# 17_FPGA_decoupling.net
KiCad netlist of a schematic drawn in Altium Designer
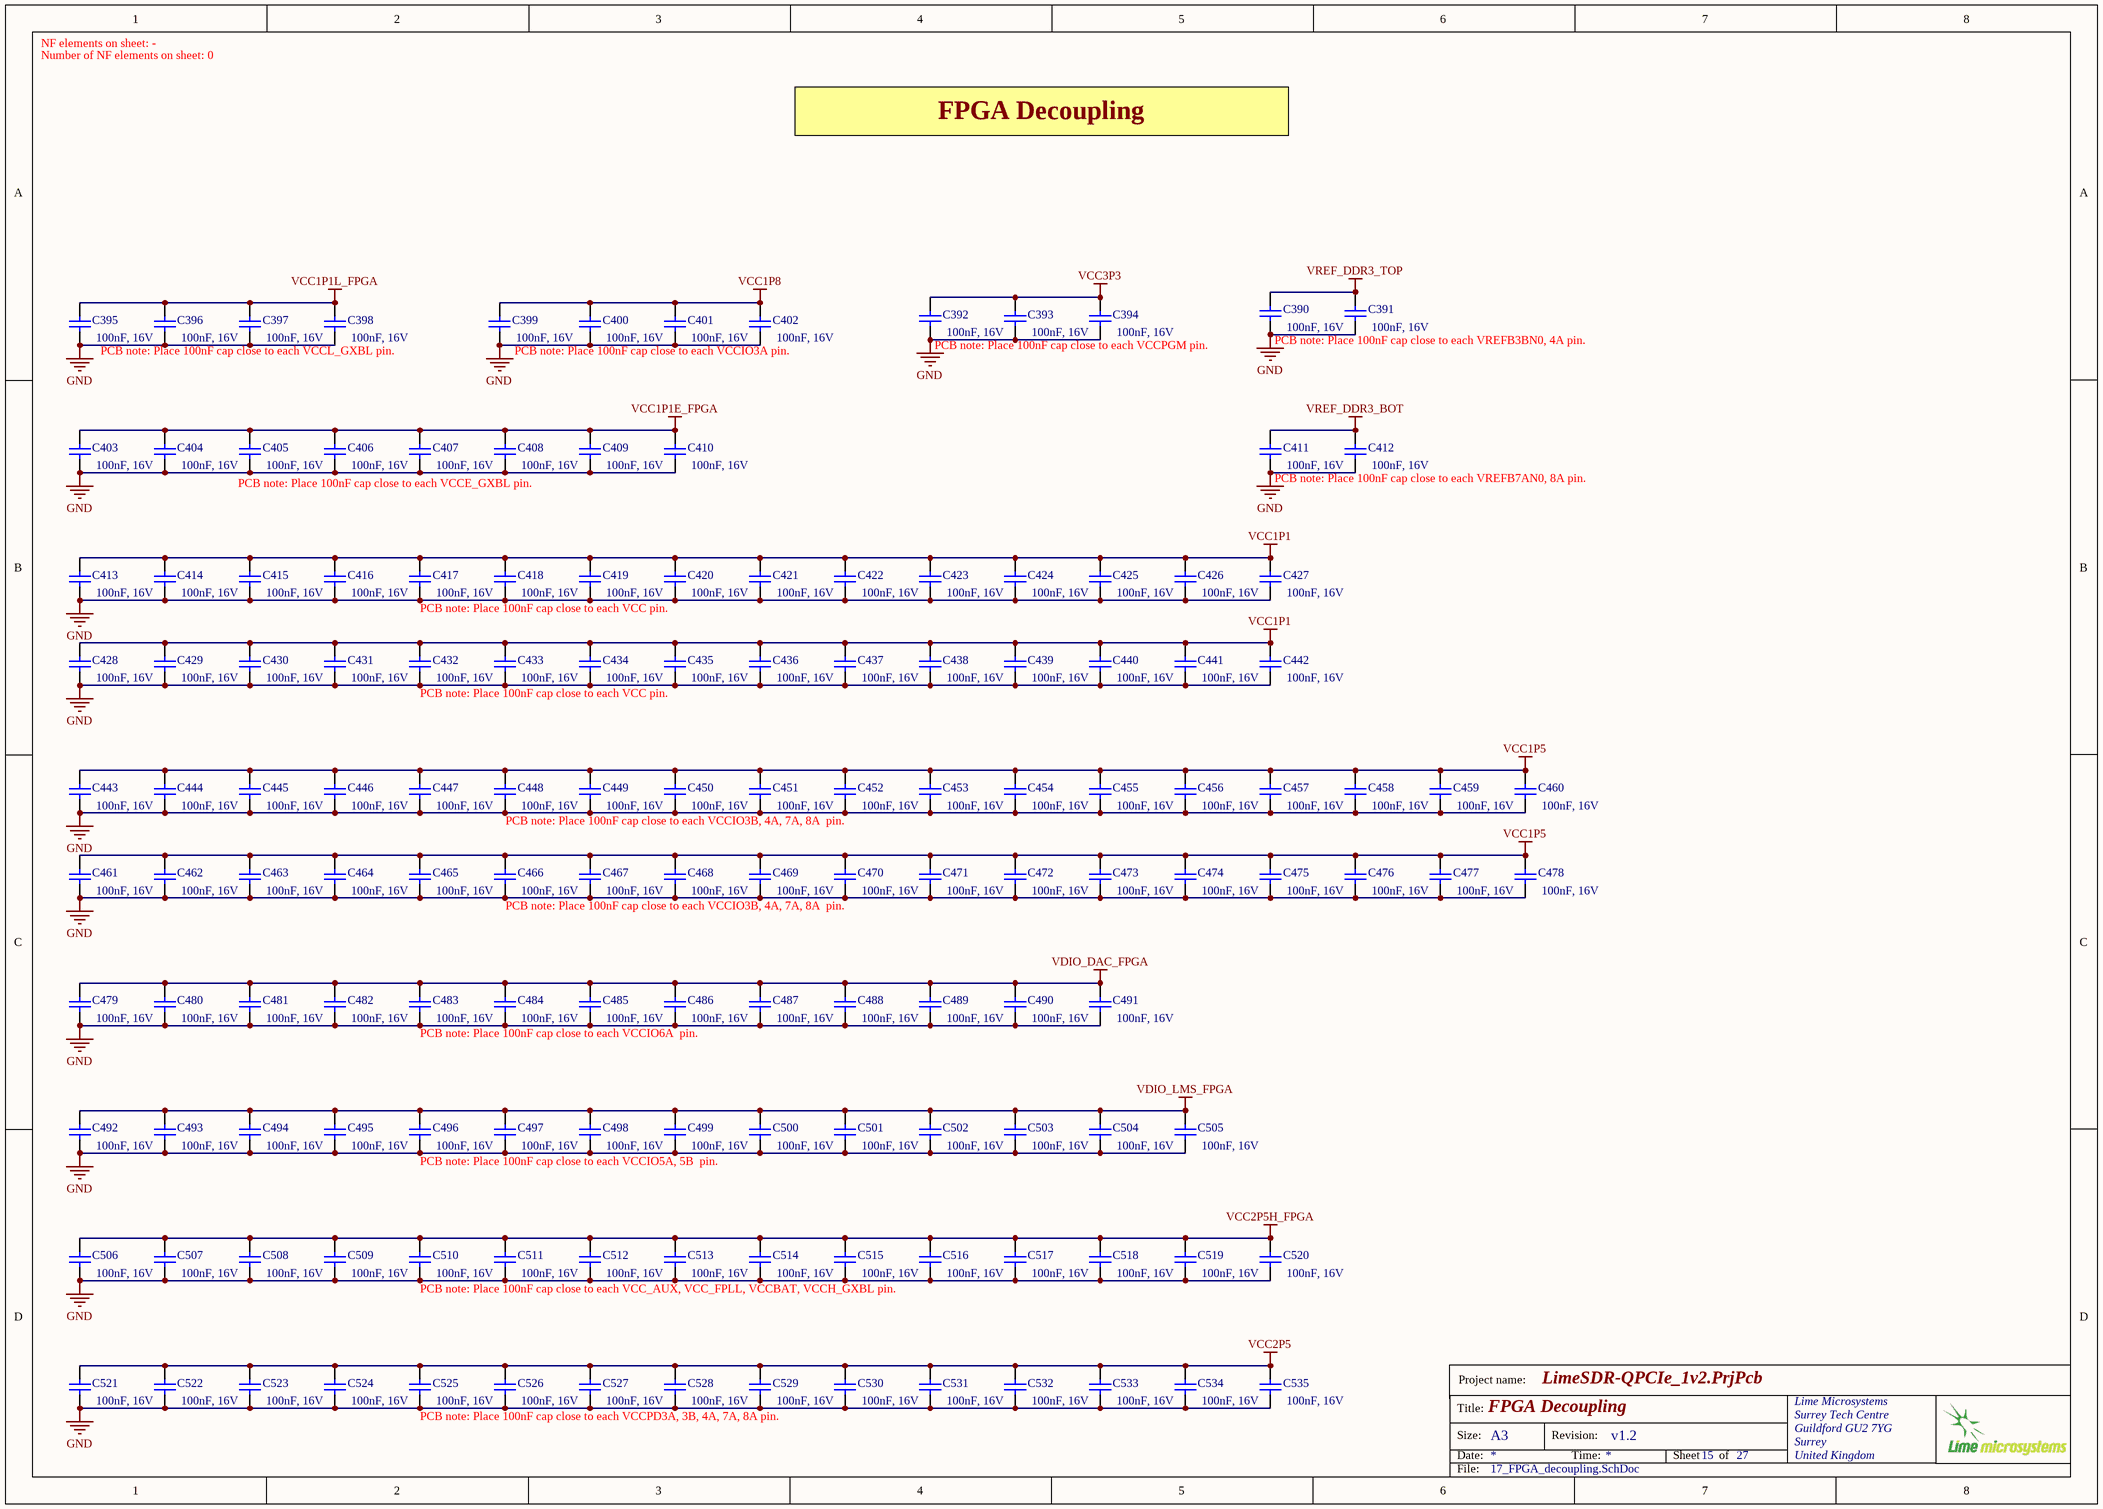
[diagram p0: 17_FPGA_decoupling.SchDoc]

(export (version "E")
  (design (tool "Eeschema 10.0.6"))
  (components
    (comp (ref "C390")
      (value "100nF, 16V")
      (footprint "CAP0402")
      (fields
        (field (name "TOLERANCE") "10 %")
        (field (name "MANUFACTURER") "Murata Electronics")
        (field (name "MANUFACTURER PART NUMBER") "GRM155R71C104KA88D")
      )
      (libsource (lib "LimeFPGAboard_schLib") (part "Cap_0603"))
    )
    (comp (ref "C391")
      (value "100nF, 16V")
      (footprint "CAP0402")
      (fields
        (field (name "TOLERANCE") "10 %")
        (field (name "MANUFACTURER") "Murata Electronics")
        (field (name "MANUFACTURER PART NUMBER") "GRM155R71C104KA88D")
      )
      (libsource (lib "LimeFPGAboard_schLib") (part "Cap_0603"))
    )
    (comp (ref "C392")
      (value "100nF, 16V")
      (footprint "CAP0402")
      (fields
        (field (name "TOLERANCE") "10 %")
        (field (name "MANUFACTURER") "Murata Electronics")
        (field (name "MANUFACTURER PART NUMBER") "GRM155R71C104KA88D")
      )
      (libsource (lib "LimeFPGAboard_schLib") (part "Cap_0603"))
    )
    (comp (ref "C393")
      (value "100nF, 16V")
      (footprint "CAP0402")
      (fields
        (field (name "TOLERANCE") "10 %")
        (field (name "MANUFACTURER") "Murata Electronics")
        (field (name "MANUFACTURER PART NUMBER") "GRM155R71C104KA88D")
      )
      (libsource (lib "LimeFPGAboard_schLib") (part "Cap_0603"))
    )
    (comp (ref "C394")
      (value "100nF, 16V")
      (footprint "CAP0402")
      (fields
        (field (name "TOLERANCE") "10 %")
        (field (name "MANUFACTURER") "Murata Electronics")
        (field (name "MANUFACTURER PART NUMBER") "GRM155R71C104KA88D")
      )
      (libsource (lib "LimeFPGAboard_schLib") (part "Cap_0603"))
    )
    (comp (ref "C395")
      (value "100nF, 16V")
      (footprint "CAP0402")
      (fields
        (field (name "TOLERANCE") "10 %")
        (field (name "MANUFACTURER") "Murata Electronics")
        (field (name "MANUFACTURER PART NUMBER") "GRM155R71C104KA88D")
      )
      (libsource (lib "LimeFPGAboard_schLib") (part "Cap_0603"))
    )
    (comp (ref "C396")
      (value "100nF, 16V")
      (footprint "CAP0402")
      (fields
        (field (name "TOLERANCE") "10 %")
        (field (name "MANUFACTURER") "Murata Electronics")
        (field (name "MANUFACTURER PART NUMBER") "GRM155R71C104KA88D")
      )
      (libsource (lib "LimeFPGAboard_schLib") (part "Cap_0603"))
    )
    (comp (ref "C397")
      (value "100nF, 16V")
      (footprint "CAP0402")
      (fields
        (field (name "TOLERANCE") "10 %")
        (field (name "MANUFACTURER") "Murata Electronics")
        (field (name "MANUFACTURER PART NUMBER") "GRM155R71C104KA88D")
      )
      (libsource (lib "LimeFPGAboard_schLib") (part "Cap_0603"))
    )
    (comp (ref "C398")
      (value "100nF, 16V")
      (footprint "CAP0402")
      (fields
        (field (name "TOLERANCE") "10 %")
        (field (name "MANUFACTURER") "Murata Electronics")
        (field (name "MANUFACTURER PART NUMBER") "GRM155R71C104KA88D")
      )
      (libsource (lib "LimeFPGAboard_schLib") (part "Cap_0603"))
    )
    (comp (ref "C399")
      (value "100nF, 16V")
      (footprint "CAP0402")
      (fields
        (field (name "TOLERANCE") "10 %")
        (field (name "MANUFACTURER") "Murata Electronics")
        (field (name "MANUFACTURER PART NUMBER") "GRM155R71C104KA88D")
      )
      (libsource (lib "LimeFPGAboard_schLib") (part "Cap_0603"))
    )
    (comp (ref "C400")
      (value "100nF, 16V")
      (footprint "CAP0402")
      (fields
        (field (name "TOLERANCE") "10 %")
        (field (name "MANUFACTURER") "Murata Electronics")
        (field (name "MANUFACTURER PART NUMBER") "GRM155R71C104KA88D")
      )
      (libsource (lib "LimeFPGAboard_schLib") (part "Cap_0603"))
    )
    (comp (ref "C401")
      (value "100nF, 16V")
      (footprint "CAP0402")
      (fields
        (field (name "TOLERANCE") "10 %")
        (field (name "MANUFACTURER") "Murata Electronics")
        (field (name "MANUFACTURER PART NUMBER") "GRM155R71C104KA88D")
      )
      (libsource (lib "LimeFPGAboard_schLib") (part "Cap_0603"))
    )
    (comp (ref "C402")
      (value "100nF, 16V")
      (footprint "CAP0402")
      (fields
        (field (name "TOLERANCE") "10 %")
        (field (name "MANUFACTURER") "Murata Electronics")
        (field (name "MANUFACTURER PART NUMBER") "GRM155R71C104KA88D")
      )
      (libsource (lib "LimeFPGAboard_schLib") (part "Cap_0603"))
    )
    (comp (ref "C403")
      (value "100nF, 16V")
      (footprint "CAP0402")
      (fields
        (field (name "TOLERANCE") "10 %")
        (field (name "MANUFACTURER") "Murata Electronics")
        (field (name "MANUFACTURER PART NUMBER") "GRM155R71C104KA88D")
      )
      (libsource (lib "LimeFPGAboard_schLib") (part "Cap_0603"))
    )
    (comp (ref "C404")
      (value "100nF, 16V")
      (footprint "CAP0402")
      (fields
        (field (name "TOLERANCE") "10 %")
        (field (name "MANUFACTURER") "Murata Electronics")
        (field (name "MANUFACTURER PART NUMBER") "GRM155R71C104KA88D")
      )
      (libsource (lib "LimeFPGAboard_schLib") (part "Cap_0603"))
    )
    (comp (ref "C405")
      (value "100nF, 16V")
      (footprint "CAP0402")
      (fields
        (field (name "TOLERANCE") "10 %")
        (field (name "MANUFACTURER") "Murata Electronics")
        (field (name "MANUFACTURER PART NUMBER") "GRM155R71C104KA88D")
      )
      (libsource (lib "LimeFPGAboard_schLib") (part "Cap_0603"))
    )
    (comp (ref "C406")
      (value "100nF, 16V")
      (footprint "CAP0402")
      (fields
        (field (name "TOLERANCE") "10 %")
        (field (name "MANUFACTURER") "Murata Electronics")
        (field (name "MANUFACTURER PART NUMBER") "GRM155R71C104KA88D")
      )
      (libsource (lib "LimeFPGAboard_schLib") (part "Cap_0603"))
    )
    (comp (ref "C407")
      (value "100nF, 16V")
      (footprint "CAP0402")
      (fields
        (field (name "TOLERANCE") "10 %")
        (field (name "MANUFACTURER") "Murata Electronics")
        (field (name "MANUFACTURER PART NUMBER") "GRM155R71C104KA88D")
      )
      (libsource (lib "LimeFPGAboard_schLib") (part "Cap_0603"))
    )
    (comp (ref "C408")
      (value "100nF, 16V")
      (footprint "CAP0402")
      (fields
        (field (name "TOLERANCE") "10 %")
        (field (name "MANUFACTURER") "Murata Electronics")
        (field (name "MANUFACTURER PART NUMBER") "GRM155R71C104KA88D")
      )
      (libsource (lib "LimeFPGAboard_schLib") (part "Cap_0603"))
    )
    (comp (ref "C409")
      (value "100nF, 16V")
      (footprint "CAP0402")
      (fields
        (field (name "TOLERANCE") "10 %")
        (field (name "MANUFACTURER") "Murata Electronics")
        (field (name "MANUFACTURER PART NUMBER") "GRM155R71C104KA88D")
      )
      (libsource (lib "LimeFPGAboard_schLib") (part "Cap_0603"))
    )
    (comp (ref "C410")
      (value "100nF, 16V")
      (footprint "CAP0402")
      (fields
        (field (name "TOLERANCE") "10 %")
        (field (name "MANUFACTURER") "Murata Electronics")
        (field (name "MANUFACTURER PART NUMBER") "GRM155R71C104KA88D")
      )
      (libsource (lib "LimeFPGAboard_schLib") (part "Cap_0603"))
    )
    (comp (ref "C411")
      (value "100nF, 16V")
      (footprint "CAP0402")
      (fields
        (field (name "TOLERANCE") "10 %")
        (field (name "MANUFACTURER") "Murata Electronics")
        (field (name "MANUFACTURER PART NUMBER") "GRM155R71C104KA88D")
      )
      (libsource (lib "LimeFPGAboard_schLib") (part "Cap_0603"))
    )
    (comp (ref "C412")
      (value "100nF, 16V")
      (footprint "CAP0402")
      (fields
        (field (name "TOLERANCE") "10 %")
        (field (name "MANUFACTURER") "Murata Electronics")
        (field (name "MANUFACTURER PART NUMBER") "GRM155R71C104KA88D")
      )
      (libsource (lib "LimeFPGAboard_schLib") (part "Cap_0603"))
    )
    (comp (ref "C413")
      (value "100nF, 16V")
      (footprint "CAP0402")
      (fields
        (field (name "TOLERANCE") "10 %")
        (field (name "MANUFACTURER") "Murata Electronics")
        (field (name "MANUFACTURER PART NUMBER") "GRM155R71C104KA88D")
      )
      (libsource (lib "LimeFPGAboard_schLib") (part "Cap_0603"))
    )
    (comp (ref "C414")
      (value "100nF, 16V")
      (footprint "CAP0402")
      (fields
        (field (name "TOLERANCE") "10 %")
        (field (name "MANUFACTURER") "Murata Electronics")
        (field (name "MANUFACTURER PART NUMBER") "GRM155R71C104KA88D")
      )
      (libsource (lib "LimeFPGAboard_schLib") (part "Cap_0603"))
    )
    (comp (ref "C415")
      (value "100nF, 16V")
      (footprint "CAP0402")
      (fields
        (field (name "TOLERANCE") "10 %")
        (field (name "MANUFACTURER") "Murata Electronics")
        (field (name "MANUFACTURER PART NUMBER") "GRM155R71C104KA88D")
      )
      (libsource (lib "LimeFPGAboard_schLib") (part "Cap_0603"))
    )
    (comp (ref "C416")
      (value "100nF, 16V")
      (footprint "CAP0402")
      (fields
        (field (name "TOLERANCE") "10 %")
        (field (name "MANUFACTURER") "Murata Electronics")
        (field (name "MANUFACTURER PART NUMBER") "GRM155R71C104KA88D")
      )
      (libsource (lib "LimeFPGAboard_schLib") (part "Cap_0603"))
    )
    (comp (ref "C417")
      (value "100nF, 16V")
      (footprint "CAP0402")
      (fields
        (field (name "TOLERANCE") "10 %")
        (field (name "MANUFACTURER") "Murata Electronics")
        (field (name "MANUFACTURER PART NUMBER") "GRM155R71C104KA88D")
      )
      (libsource (lib "LimeFPGAboard_schLib") (part "Cap_0603"))
    )
    (comp (ref "C418")
      (value "100nF, 16V")
      (footprint "CAP0402")
      (fields
        (field (name "TOLERANCE") "10 %")
        (field (name "MANUFACTURER") "Murata Electronics")
        (field (name "MANUFACTURER PART NUMBER") "GRM155R71C104KA88D")
      )
      (libsource (lib "LimeFPGAboard_schLib") (part "Cap_0603"))
    )
    (comp (ref "C419")
      (value "100nF, 16V")
      (footprint "CAP0402")
      (fields
        (field (name "TOLERANCE") "10 %")
        (field (name "MANUFACTURER") "Murata Electronics")
        (field (name "MANUFACTURER PART NUMBER") "GRM155R71C104KA88D")
      )
      (libsource (lib "LimeFPGAboard_schLib") (part "Cap_0603"))
    )
    (comp (ref "C420")
      (value "100nF, 16V")
      (footprint "CAP0402")
      (fields
        (field (name "TOLERANCE") "10 %")
        (field (name "MANUFACTURER") "Murata Electronics")
        (field (name "MANUFACTURER PART NUMBER") "GRM155R71C104KA88D")
      )
      (libsource (lib "LimeFPGAboard_schLib") (part "Cap_0603"))
    )
    (comp (ref "C421")
      (value "100nF, 16V")
      (footprint "CAP0402")
      (fields
        (field (name "TOLERANCE") "10 %")
        (field (name "MANUFACTURER") "Murata Electronics")
        (field (name "MANUFACTURER PART NUMBER") "GRM155R71C104KA88D")
      )
      (libsource (lib "LimeFPGAboard_schLib") (part "Cap_0603"))
    )
    (comp (ref "C422")
      (value "100nF, 16V")
      (footprint "CAP0402")
      (fields
        (field (name "TOLERANCE") "10 %")
        (field (name "MANUFACTURER") "Murata Electronics")
        (field (name "MANUFACTURER PART NUMBER") "GRM155R71C104KA88D")
      )
      (libsource (lib "LimeFPGAboard_schLib") (part "Cap_0603"))
    )
    (comp (ref "C423")
      (value "100nF, 16V")
      (footprint "CAP0402")
      (fields
        (field (name "TOLERANCE") "10 %")
        (field (name "MANUFACTURER") "Murata Electronics")
        (field (name "MANUFACTURER PART NUMBER") "GRM155R71C104KA88D")
      )
      (libsource (lib "LimeFPGAboard_schLib") (part "Cap_0603"))
    )
    (comp (ref "C424")
      (value "100nF, 16V")
      (footprint "CAP0402")
      (fields
        (field (name "TOLERANCE") "10 %")
        (field (name "MANUFACTURER") "Murata Electronics")
        (field (name "MANUFACTURER PART NUMBER") "GRM155R71C104KA88D")
      )
      (libsource (lib "LimeFPGAboard_schLib") (part "Cap_0603"))
    )
    (comp (ref "C425")
      (value "100nF, 16V")
      (footprint "CAP0402")
      (fields
        (field (name "TOLERANCE") "10 %")
        (field (name "MANUFACTURER") "Murata Electronics")
        (field (name "MANUFACTURER PART NUMBER") "GRM155R71C104KA88D")
      )
      (libsource (lib "LimeFPGAboard_schLib") (part "Cap_0603"))
    )
    (comp (ref "C426")
      (value "100nF, 16V")
      (footprint "CAP0402")
      (fields
        (field (name "TOLERANCE") "10 %")
        (field (name "MANUFACTURER") "Murata Electronics")
        (field (name "MANUFACTURER PART NUMBER") "GRM155R71C104KA88D")
      )
      (libsource (lib "LimeFPGAboard_schLib") (part "Cap_0603"))
    )
    (comp (ref "C427")
      (value "100nF, 16V")
      (footprint "CAP0402")
      (fields
        (field (name "TOLERANCE") "10 %")
        (field (name "MANUFACTURER") "Murata Electronics")
        (field (name "MANUFACTURER PART NUMBER") "GRM155R71C104KA88D")
      )
      (libsource (lib "LimeFPGAboard_schLib") (part "Cap_0603"))
    )
    (comp (ref "C428")
      (value "100nF, 16V")
      (footprint "CAP0402")
      (fields
        (field (name "TOLERANCE") "10 %")
        (field (name "MANUFACTURER") "Murata Electronics")
        (field (name "MANUFACTURER PART NUMBER") "GRM155R71C104KA88D")
      )
      (libsource (lib "LimeFPGAboard_schLib") (part "Cap_0603"))
    )
    (comp (ref "C429")
      (value "100nF, 16V")
      (footprint "CAP0402")
      (fields
        (field (name "TOLERANCE") "10 %")
        (field (name "MANUFACTURER") "Murata Electronics")
        (field (name "MANUFACTURER PART NUMBER") "GRM155R71C104KA88D")
      )
      (libsource (lib "LimeFPGAboard_schLib") (part "Cap_0603"))
    )
    (comp (ref "C430")
      (value "100nF, 16V")
      (footprint "CAP0402")
      (fields
        (field (name "TOLERANCE") "10 %")
        (field (name "MANUFACTURER") "Murata Electronics")
        (field (name "MANUFACTURER PART NUMBER") "GRM155R71C104KA88D")
      )
      (libsource (lib "LimeFPGAboard_schLib") (part "Cap_0603"))
    )
    (comp (ref "C431")
      (value "100nF, 16V")
      (footprint "CAP0402")
      (fields
        (field (name "TOLERANCE") "10 %")
        (field (name "MANUFACTURER") "Murata Electronics")
        (field (name "MANUFACTURER PART NUMBER") "GRM155R71C104KA88D")
      )
      (libsource (lib "LimeFPGAboard_schLib") (part "Cap_0603"))
    )
    (comp (ref "C432")
      (value "100nF, 16V")
      (footprint "CAP0402")
      (fields
        (field (name "TOLERANCE") "10 %")
        (field (name "MANUFACTURER") "Murata Electronics")
        (field (name "MANUFACTURER PART NUMBER") "GRM155R71C104KA88D")
      )
      (libsource (lib "LimeFPGAboard_schLib") (part "Cap_0603"))
    )
    (comp (ref "C433")
      (value "100nF, 16V")
      (footprint "CAP0402")
      (fields
        (field (name "TOLERANCE") "10 %")
        (field (name "MANUFACTURER") "Murata Electronics")
        (field (name "MANUFACTURER PART NUMBER") "GRM155R71C104KA88D")
      )
      (libsource (lib "LimeFPGAboard_schLib") (part "Cap_0603"))
    )
    (comp (ref "C434")
      (value "100nF, 16V")
      (footprint "CAP0402")
      (fields
        (field (name "TOLERANCE") "10 %")
        (field (name "MANUFACTURER") "Murata Electronics")
        (field (name "MANUFACTURER PART NUMBER") "GRM155R71C104KA88D")
      )
      (libsource (lib "LimeFPGAboard_schLib") (part "Cap_0603"))
    )
    (comp (ref "C435")
      (value "100nF, 16V")
      (footprint "CAP0402")
      (fields
        (field (name "TOLERANCE") "10 %")
        (field (name "MANUFACTURER") "Murata Electronics")
        (field (name "MANUFACTURER PART NUMBER") "GRM155R71C104KA88D")
      )
      (libsource (lib "LimeFPGAboard_schLib") (part "Cap_0603"))
    )
    (comp (ref "C436")
      (value "100nF, 16V")
      (footprint "CAP0402")
      (fields
        (field (name "TOLERANCE") "10 %")
        (field (name "MANUFACTURER") "Murata Electronics")
        (field (name "MANUFACTURER PART NUMBER") "GRM155R71C104KA88D")
      )
      (libsource (lib "LimeFPGAboard_schLib") (part "Cap_0603"))
    )
    (comp (ref "C437")
      (value "100nF, 16V")
      (footprint "CAP0402")
      (fields
        (field (name "TOLERANCE") "10 %")
        (field (name "MANUFACTURER") "Murata Electronics")
        (field (name "MANUFACTURER PART NUMBER") "GRM155R71C104KA88D")
      )
      (libsource (lib "LimeFPGAboard_schLib") (part "Cap_0603"))
    )
    (comp (ref "C438")
      (value "100nF, 16V")
      (footprint "CAP0402")
      (fields
        (field (name "TOLERANCE") "10 %")
        (field (name "MANUFACTURER") "Murata Electronics")
        (field (name "MANUFACTURER PART NUMBER") "GRM155R71C104KA88D")
      )
      (libsource (lib "LimeFPGAboard_schLib") (part "Cap_0603"))
    )
    (comp (ref "C439")
      (value "100nF, 16V")
      (footprint "CAP0402")
      (fields
        (field (name "TOLERANCE") "10 %")
        (field (name "MANUFACTURER") "Murata Electronics")
        (field (name "MANUFACTURER PART NUMBER") "GRM155R71C104KA88D")
      )
      (libsource (lib "LimeFPGAboard_schLib") (part "Cap_0603"))
    )
    (comp (ref "C440")
      (value "100nF, 16V")
      (footprint "CAP0402")
      (fields
        (field (name "TOLERANCE") "10 %")
        (field (name "MANUFACTURER") "Murata Electronics")
        (field (name "MANUFACTURER PART NUMBER") "GRM155R71C104KA88D")
      )
      (libsource (lib "LimeFPGAboard_schLib") (part "Cap_0603"))
    )
    (comp (ref "C441")
      (value "100nF, 16V")
      (footprint "CAP0402")
      (fields
        (field (name "TOLERANCE") "10 %")
        (field (name "MANUFACTURER") "Murata Electronics")
        (field (name "MANUFACTURER PART NUMBER") "GRM155R71C104KA88D")
      )
      (libsource (lib "LimeFPGAboard_schLib") (part "Cap_0603"))
    )
    (comp (ref "C442")
      (value "100nF, 16V")
      (footprint "CAP0402")
      (fields
        (field (name "TOLERANCE") "10 %")
        (field (name "MANUFACTURER") "Murata Electronics")
        (field (name "MANUFACTURER PART NUMBER") "GRM155R71C104KA88D")
      )
      (libsource (lib "LimeFPGAboard_schLib") (part "Cap_0603"))
    )
    (comp (ref "C443")
      (value "100nF, 16V")
      (footprint "CAP0402")
      (fields
        (field (name "TOLERANCE") "10 %")
        (field (name "MANUFACTURER") "Murata Electronics")
        (field (name "MANUFACTURER PART NUMBER") "GRM155R71C104KA88D")
      )
      (libsource (lib "LimeFPGAboard_schLib") (part "Cap_0603"))
    )
    (comp (ref "C444")
      (value "100nF, 16V")
      (footprint "CAP0402")
      (fields
        (field (name "TOLERANCE") "10 %")
        (field (name "MANUFACTURER") "Murata Electronics")
        (field (name "MANUFACTURER PART NUMBER") "GRM155R71C104KA88D")
      )
      (libsource (lib "LimeFPGAboard_schLib") (part "Cap_0603"))
    )
    (comp (ref "C445")
      (value "100nF, 16V")
      (footprint "CAP0402")
      (fields
        (field (name "TOLERANCE") "10 %")
        (field (name "MANUFACTURER") "Murata Electronics")
        (field (name "MANUFACTURER PART NUMBER") "GRM155R71C104KA88D")
      )
      (libsource (lib "LimeFPGAboard_schLib") (part "Cap_0603"))
    )
    (comp (ref "C446")
      (value "100nF, 16V")
      (footprint "CAP0402")
      (fields
        (field (name "TOLERANCE") "10 %")
        (field (name "MANUFACTURER") "Murata Electronics")
        (field (name "MANUFACTURER PART NUMBER") "GRM155R71C104KA88D")
      )
      (libsource (lib "LimeFPGAboard_schLib") (part "Cap_0603"))
    )
    (comp (ref "C447")
      (value "100nF, 16V")
      (footprint "CAP0402")
      (fields
        (field (name "TOLERANCE") "10 %")
        (field (name "MANUFACTURER") "Murata Electronics")
        (field (name "MANUFACTURER PART NUMBER") "GRM155R71C104KA88D")
      )
      (libsource (lib "LimeFPGAboard_schLib") (part "Cap_0603"))
    )
    (comp (ref "C448")
      (value "100nF, 16V")
      (footprint "CAP0402")
      (fields
        (field (name "TOLERANCE") "10 %")
        (field (name "MANUFACTURER") "Murata Electronics")
        (field (name "MANUFACTURER PART NUMBER") "GRM155R71C104KA88D")
      )
      (libsource (lib "LimeFPGAboard_schLib") (part "Cap_0603"))
    )
    (comp (ref "C449")
      (value "100nF, 16V")
      (footprint "CAP0402")
      (fields
        (field (name "TOLERANCE") "10 %")
        (field (name "MANUFACTURER") "Murata Electronics")
        (field (name "MANUFACTURER PART NUMBER") "GRM155R71C104KA88D")
      )
      (libsource (lib "LimeFPGAboard_schLib") (part "Cap_0603"))
    )
    (comp (ref "C450")
      (value "100nF, 16V")
      (footprint "CAP0402")
      (fields
        (field (name "TOLERANCE") "10 %")
        (field (name "MANUFACTURER") "Murata Electronics")
        (field (name "MANUFACTURER PART NUMBER") "GRM155R71C104KA88D")
      )
      (libsource (lib "LimeFPGAboard_schLib") (part "Cap_0603"))
    )
    (comp (ref "C451")
      (value "100nF, 16V")
      (footprint "CAP0402")
      (fields
        (field (name "TOLERANCE") "10 %")
        (field (name "MANUFACTURER") "Murata Electronics")
        (field (name "MANUFACTURER PART NUMBER") "GRM155R71C104KA88D")
      )
      (libsource (lib "LimeFPGAboard_schLib") (part "Cap_0603"))
    )
    (comp (ref "C452")
      (value "100nF, 16V")
      (footprint "CAP0402")
      (fields
        (field (name "TOLERANCE") "10 %")
        (field (name "MANUFACTURER") "Murata Electronics")
        (field (name "MANUFACTURER PART NUMBER") "GRM155R71C104KA88D")
      )
      (libsource (lib "LimeFPGAboard_schLib") (part "Cap_0603"))
    )
    (comp (ref "C453")
      (value "100nF, 16V")
      (footprint "CAP0402")
      (fields
        (field (name "TOLERANCE") "10 %")
        (field (name "MANUFACTURER") "Murata Electronics")
        (field (name "MANUFACTURER PART NUMBER") "GRM155R71C104KA88D")
      )
      (libsource (lib "LimeFPGAboard_schLib") (part "Cap_0603"))
    )
    (comp (ref "C454")
      (value "100nF, 16V")
      (footprint "CAP0402")
      (fields
        (field (name "TOLERANCE") "10 %")
        (field (name "MANUFACTURER") "Murata Electronics")
        (field (name "MANUFACTURER PART NUMBER") "GRM155R71C104KA88D")
      )
      (libsource (lib "LimeFPGAboard_schLib") (part "Cap_0603"))
    )
    (comp (ref "C455")
      (value "100nF, 16V")
      (footprint "CAP0402")
      (fields
        (field (name "TOLERANCE") "10 %")
        (field (name "MANUFACTURER") "Murata Electronics")
        (field (name "MANUFACTURER PART NUMBER") "GRM155R71C104KA88D")
      )
      (libsource (lib "LimeFPGAboard_schLib") (part "Cap_0603"))
    )
    (comp (ref "C456")
      (value "100nF, 16V")
      (footprint "CAP0402")
      (fields
        (field (name "TOLERANCE") "10 %")
        (field (name "MANUFACTURER") "Murata Electronics")
        (field (name "MANUFACTURER PART NUMBER") "GRM155R71C104KA88D")
      )
      (libsource (lib "LimeFPGAboard_schLib") (part "Cap_0603"))
    )
    (comp (ref "C457")
      (value "100nF, 16V")
      (footprint "CAP0402")
      (fields
        (field (name "TOLERANCE") "10 %")
        (field (name "MANUFACTURER") "Murata Electronics")
        (field (name "MANUFACTURER PART NUMBER") "GRM155R71C104KA88D")
      )
      (libsource (lib "LimeFPGAboard_schLib") (part "Cap_0603"))
    )
    (comp (ref "C458")
      (value "100nF, 16V")
      (footprint "CAP0402")
      (fields
        (field (name "TOLERANCE") "10 %")
        (field (name "MANUFACTURER") "Murata Electronics")
        (field (name "MANUFACTURER PART NUMBER") "GRM155R71C104KA88D")
      )
      (libsource (lib "LimeFPGAboard_schLib") (part "Cap_0603"))
    )
    (comp (ref "C459")
      (value "100nF, 16V")
      (footprint "CAP0402")
      (fields
        (field (name "TOLERANCE") "10 %")
        (field (name "MANUFACTURER") "Murata Electronics")
        (field (name "MANUFACTURER PART NUMBER") "GRM155R71C104KA88D")
      )
      (libsource (lib "LimeFPGAboard_schLib") (part "Cap_0603"))
    )
    (comp (ref "C460")
      (value "100nF, 16V")
      (footprint "CAP0402")
      (fields
        (field (name "TOLERANCE") "10 %")
        (field (name "MANUFACTURER") "Murata Electronics")
        (field (name "MANUFACTURER PART NUMBER") "GRM155R71C104KA88D")
      )
      (libsource (lib "LimeFPGAboard_schLib") (part "Cap_0603"))
    )
    (comp (ref "C461")
      (value "100nF, 16V")
      (footprint "CAP0402")
      (fields
        (field (name "TOLERANCE") "10 %")
        (field (name "MANUFACTURER") "Murata Electronics")
        (field (name "MANUFACTURER PART NUMBER") "GRM155R71C104KA88D")
      )
      (libsource (lib "LimeFPGAboard_schLib") (part "Cap_0603"))
    )
    (comp (ref "C462")
      (value "100nF, 16V")
      (footprint "CAP0402")
      (fields
        (field (name "TOLERANCE") "10 %")
        (field (name "MANUFACTURER") "Murata Electronics")
        (field (name "MANUFACTURER PART NUMBER") "GRM155R71C104KA88D")
      )
      (libsource (lib "LimeFPGAboard_schLib") (part "Cap_0603"))
    )
    (comp (ref "C463")
      (value "100nF, 16V")
      (footprint "CAP0402")
      (fields
        (field (name "TOLERANCE") "10 %")
        (field (name "MANUFACTURER") "Murata Electronics")
        (field (name "MANUFACTURER PART NUMBER") "GRM155R71C104KA88D")
      )
      (libsource (lib "LimeFPGAboard_schLib") (part "Cap_0603"))
    )
    (comp (ref "C464")
      (value "100nF, 16V")
      (footprint "CAP0402")
      (fields
        (field (name "TOLERANCE") "10 %")
        (field (name "MANUFACTURER") "Murata Electronics")
        (field (name "MANUFACTURER PART NUMBER") "GRM155R71C104KA88D")
      )
      (libsource (lib "LimeFPGAboard_schLib") (part "Cap_0603"))
    )
    (comp (ref "C465")
      (value "100nF, 16V")
      (footprint "CAP0402")
      (fields
        (field (name "TOLERANCE") "10 %")
        (field (name "MANUFACTURER") "Murata Electronics")
        (field (name "MANUFACTURER PART NUMBER") "GRM155R71C104KA88D")
      )
      (libsource (lib "LimeFPGAboard_schLib") (part "Cap_0603"))
    )
    (comp (ref "C466")
      (value "100nF, 16V")
      (footprint "CAP0402")
      (fields
        (field (name "TOLERANCE") "10 %")
        (field (name "MANUFACTURER") "Murata Electronics")
        (field (name "MANUFACTURER PART NUMBER") "GRM155R71C104KA88D")
      )
      (libsource (lib "LimeFPGAboard_schLib") (part "Cap_0603"))
    )
    (comp (ref "C467")
      (value "100nF, 16V")
      (footprint "CAP0402")
      (fields
        (field (name "TOLERANCE") "10 %")
        (field (name "MANUFACTURER") "Murata Electronics")
        (field (name "MANUFACTURER PART NUMBER") "GRM155R71C104KA88D")
      )
      (libsource (lib "LimeFPGAboard_schLib") (part "Cap_0603"))
    )
    (comp (ref "C468")
      (value "100nF, 16V")
      (footprint "CAP0402")
      (fields
        (field (name "TOLERANCE") "10 %")
        (field (name "MANUFACTURER") "Murata Electronics")
        (field (name "MANUFACTURER PART NUMBER") "GRM155R71C104KA88D")
      )
      (libsource (lib "LimeFPGAboard_schLib") (part "Cap_0603"))
    )
    (comp (ref "C469")
      (value "100nF, 16V")
      (footprint "CAP0402")
      (fields
        (field (name "TOLERANCE") "10 %")
        (field (name "MANUFACTURER") "Murata Electronics")
        (field (name "MANUFACTURER PART NUMBER") "GRM155R71C104KA88D")
      )
      (libsource (lib "LimeFPGAboard_schLib") (part "Cap_0603"))
    )
    (comp (ref "C470")
      (value "100nF, 16V")
      (footprint "CAP0402")
      (fields
        (field (name "TOLERANCE") "10 %")
        (field (name "MANUFACTURER") "Murata Electronics")
        (field (name "MANUFACTURER PART NUMBER") "GRM155R71C104KA88D")
      )
      (libsource (lib "LimeFPGAboard_schLib") (part "Cap_0603"))
    )
    (comp (ref "C471")
      (value "100nF, 16V")
      (footprint "CAP0402")
      (fields
        (field (name "TOLERANCE") "10 %")
        (field (name "MANUFACTURER") "Murata Electronics")
        (field (name "MANUFACTURER PART NUMBER") "GRM155R71C104KA88D")
      )
      (libsource (lib "LimeFPGAboard_schLib") (part "Cap_0603"))
    )
    (comp (ref "C472")
      (value "100nF, 16V")
      (footprint "CAP0402")
      (fields
        (field (name "TOLERANCE") "10 %")
        (field (name "MANUFACTURER") "Murata Electronics")
        (field (name "MANUFACTURER PART NUMBER") "GRM155R71C104KA88D")
      )
      (libsource (lib "LimeFPGAboard_schLib") (part "Cap_0603"))
    )
    (comp (ref "C473")
      (value "100nF, 16V")
      (footprint "CAP0402")
      (fields
        (field (name "TOLERANCE") "10 %")
        (field (name "MANUFACTURER") "Murata Electronics")
        (field (name "MANUFACTURER PART NUMBER") "GRM155R71C104KA88D")
      )
      (libsource (lib "LimeFPGAboard_schLib") (part "Cap_0603"))
    )
    (comp (ref "C474")
      (value "100nF, 16V")
      (footprint "CAP0402")
      (fields
        (field (name "TOLERANCE") "10 %")
        (field (name "MANUFACTURER") "Murata Electronics")
        (field (name "MANUFACTURER PART NUMBER") "GRM155R71C104KA88D")
      )
      (libsource (lib "LimeFPGAboard_schLib") (part "Cap_0603"))
    )
    (comp (ref "C475")
      (value "100nF, 16V")
      (footprint "CAP0402")
      (fields
        (field (name "TOLERANCE") "10 %")
        (field (name "MANUFACTURER") "Murata Electronics")
        (field (name "MANUFACTURER PART NUMBER") "GRM155R71C104KA88D")
      )
      (libsource (lib "LimeFPGAboard_schLib") (part "Cap_0603"))
    )
    (comp (ref "C476")
      (value "100nF, 16V")
      (footprint "CAP0402")
      (fields
        (field (name "TOLERANCE") "10 %")
        (field (name "MANUFACTURER") "Murata Electronics")
        (field (name "MANUFACTURER PART NUMBER") "GRM155R71C104KA88D")
      )
      (libsource (lib "LimeFPGAboard_schLib") (part "Cap_0603"))
    )
    (comp (ref "C477")
      (value "100nF, 16V")
      (footprint "CAP0402")
      (fields
        (field (name "TOLERANCE") "10 %")
        (field (name "MANUFACTURER") "Murata Electronics")
        (field (name "MANUFACTURER PART NUMBER") "GRM155R71C104KA88D")
      )
      (libsource (lib "LimeFPGAboard_schLib") (part "Cap_0603"))
    )
    (comp (ref "C478")
      (value "100nF, 16V")
      (footprint "CAP0402")
      (fields
        (field (name "TOLERANCE") "10 %")
        (field (name "MANUFACTURER") "Murata Electronics")
        (field (name "MANUFACTURER PART NUMBER") "GRM155R71C104KA88D")
      )
      (libsource (lib "LimeFPGAboard_schLib") (part "Cap_0603"))
    )
    (comp (ref "C479")
      (value "100nF, 16V")
      (footprint "CAP0402")
      (fields
        (field (name "TOLERANCE") "10 %")
        (field (name "MANUFACTURER") "Murata Electronics")
        (field (name "MANUFACTURER PART NUMBER") "GRM155R71C104KA88D")
      )
      (libsource (lib "LimeFPGAboard_schLib") (part "Cap_0603"))
    )
    (comp (ref "C480")
      (value "100nF, 16V")
      (footprint "CAP0402")
      (fields
        (field (name "TOLERANCE") "10 %")
        (field (name "MANUFACTURER") "Murata Electronics")
        (field (name "MANUFACTURER PART NUMBER") "GRM155R71C104KA88D")
      )
      (libsource (lib "LimeFPGAboard_schLib") (part "Cap_0603"))
    )
    (comp (ref "C481")
      (value "100nF, 16V")
      (footprint "CAP0402")
      (fields
        (field (name "TOLERANCE") "10 %")
        (field (name "MANUFACTURER") "Murata Electronics")
        (field (name "MANUFACTURER PART NUMBER") "GRM155R71C104KA88D")
      )
      (libsource (lib "LimeFPGAboard_schLib") (part "Cap_0603"))
    )
    (comp (ref "C482")
      (value "100nF, 16V")
      (footprint "CAP0402")
      (fields
        (field (name "TOLERANCE") "10 %")
        (field (name "MANUFACTURER") "Murata Electronics")
        (field (name "MANUFACTURER PART NUMBER") "GRM155R71C104KA88D")
      )
      (libsource (lib "LimeFPGAboard_schLib") (part "Cap_0603"))
    )
    (comp (ref "C483")
      (value "100nF, 16V")
      (footprint "CAP0402")
      (fields
        (field (name "TOLERANCE") "10 %")
        (field (name "MANUFACTURER") "Murata Electronics")
        (field (name "MANUFACTURER PART NUMBER") "GRM155R71C104KA88D")
      )
      (libsource (lib "LimeFPGAboard_schLib") (part "Cap_0603"))
    )
    (comp (ref "C484")
      (value "100nF, 16V")
      (footprint "CAP0402")
      (fields
        (field (name "TOLERANCE") "10 %")
        (field (name "MANUFACTURER") "Murata Electronics")
        (field (name "MANUFACTURER PART NUMBER") "GRM155R71C104KA88D")
      )
      (libsource (lib "LimeFPGAboard_schLib") (part "Cap_0603"))
    )
    (comp (ref "C485")
      (value "100nF, 16V")
      (footprint "CAP0402")
      (fields
        (field (name "TOLERANCE") "10 %")
        (field (name "MANUFACTURER") "Murata Electronics")
        (field (name "MANUFACTURER PART NUMBER") "GRM155R71C104KA88D")
      )
      (libsource (lib "LimeFPGAboard_schLib") (part "Cap_0603"))
    )
    (comp (ref "C486")
      (value "100nF, 16V")
      (footprint "CAP0402")
      (fields
        (field (name "TOLERANCE") "10 %")
        (field (name "MANUFACTURER") "Murata Electronics")
        (field (name "MANUFACTURER PART NUMBER") "GRM155R71C104KA88D")
      )
      (libsource (lib "LimeFPGAboard_schLib") (part "Cap_0603"))
    )
    (comp (ref "C487")
      (value "100nF, 16V")
      (footprint "CAP0402")
      (fields
        (field (name "TOLERANCE") "10 %")
        (field (name "MANUFACTURER") "Murata Electronics")
        (field (name "MANUFACTURER PART NUMBER") "GRM155R71C104KA88D")
      )
      (libsource (lib "LimeFPGAboard_schLib") (part "Cap_0603"))
    )
    (comp (ref "C488")
      (value "100nF, 16V")
      (footprint "CAP0402")
      (fields
        (field (name "TOLERANCE") "10 %")
        (field (name "MANUFACTURER") "Murata Electronics")
        (field (name "MANUFACTURER PART NUMBER") "GRM155R71C104KA88D")
      )
      (libsource (lib "LimeFPGAboard_schLib") (part "Cap_0603"))
    )
    (comp (ref "C489")
      (value "100nF, 16V")
      (footprint "CAP0402")
      (fields
        (field (name "TOLERANCE") "10 %")
        (field (name "MANUFACTURER") "Murata Electronics")
        (field (name "MANUFACTURER PART NUMBER") "GRM155R71C104KA88D")
      )
      (libsource (lib "LimeFPGAboard_schLib") (part "Cap_0603"))
    )
    (comp (ref "C490")
      (value "100nF, 16V")
      (footprint "CAP0402")
      (fields
        (field (name "TOLERANCE") "10 %")
        (field (name "MANUFACTURER") "Murata Electronics")
        (field (name "MANUFACTURER PART NUMBER") "GRM155R71C104KA88D")
      )
      (libsource (lib "LimeFPGAboard_schLib") (part "Cap_0603"))
    )
    (comp (ref "C491")
      (value "100nF, 16V")
      (footprint "CAP0402")
      (fields
        (field (name "TOLERANCE") "10 %")
        (field (name "MANUFACTURER") "Murata Electronics")
        (field (name "MANUFACTURER PART NUMBER") "GRM155R71C104KA88D")
      )
      (libsource (lib "LimeFPGAboard_schLib") (part "Cap_0603"))
    )
    (comp (ref "C492")
      (value "100nF, 16V")
      (footprint "CAP0402")
      (fields
        (field (name "TOLERANCE") "10 %")
        (field (name "MANUFACTURER") "Murata Electronics")
        (field (name "MANUFACTURER PART NUMBER") "GRM155R71C104KA88D")
      )
      (libsource (lib "LimeFPGAboard_schLib") (part "Cap_0603"))
    )
    (comp (ref "C493")
      (value "100nF, 16V")
      (footprint "CAP0402")
      (fields
        (field (name "TOLERANCE") "10 %")
        (field (name "MANUFACTURER") "Murata Electronics")
        (field (name "MANUFACTURER PART NUMBER") "GRM155R71C104KA88D")
      )
      (libsource (lib "LimeFPGAboard_schLib") (part "Cap_0603"))
    )
    (comp (ref "C494")
      (value "100nF, 16V")
      (footprint "CAP0402")
      (fields
        (field (name "TOLERANCE") "10 %")
        (field (name "MANUFACTURER") "Murata Electronics")
        (field (name "MANUFACTURER PART NUMBER") "GRM155R71C104KA88D")
      )
      (libsource (lib "LimeFPGAboard_schLib") (part "Cap_0603"))
    )
    (comp (ref "C495")
      (value "100nF, 16V")
      (footprint "CAP0402")
      (fields
        (field (name "TOLERANCE") "10 %")
        (field (name "MANUFACTURER") "Murata Electronics")
        (field (name "MANUFACTURER PART NUMBER") "GRM155R71C104KA88D")
      )
      (libsource (lib "LimeFPGAboard_schLib") (part "Cap_0603"))
    )
    (comp (ref "C496")
      (value "100nF, 16V")
      (footprint "CAP0402")
      (fields
        (field (name "TOLERANCE") "10 %")
        (field (name "MANUFACTURER") "Murata Electronics")
        (field (name "MANUFACTURER PART NUMBER") "GRM155R71C104KA88D")
      )
      (libsource (lib "LimeFPGAboard_schLib") (part "Cap_0603"))
    )
    (comp (ref "C497")
      (value "100nF, 16V")
      (footprint "CAP0402")
      (fields
        (field (name "TOLERANCE") "10 %")
        (field (name "MANUFACTURER") "Murata Electronics")
        (field (name "MANUFACTURER PART NUMBER") "GRM155R71C104KA88D")
      )
      (libsource (lib "LimeFPGAboard_schLib") (part "Cap_0603"))
    )
    (comp (ref "C498")
      (value "100nF, 16V")
      (footprint "CAP0402")
      (fields
        (field (name "TOLERANCE") "10 %")
        (field (name "MANUFACTURER") "Murata Electronics")
        (field (name "MANUFACTURER PART NUMBER") "GRM155R71C104KA88D")
      )
      (libsource (lib "LimeFPGAboard_schLib") (part "Cap_0603"))
    )
    (comp (ref "C499")
      (value "100nF, 16V")
      (footprint "CAP0402")
      (fields
        (field (name "TOLERANCE") "10 %")
        (field (name "MANUFACTURER") "Murata Electronics")
        (field (name "MANUFACTURER PART NUMBER") "GRM155R71C104KA88D")
      )
      (libsource (lib "LimeFPGAboard_schLib") (part "Cap_0603"))
    )
    (comp (ref "C500")
      (value "100nF, 16V")
      (footprint "CAP0402")
      (fields
        (field (name "TOLERANCE") "10 %")
        (field (name "MANUFACTURER") "Murata Electronics")
        (field (name "MANUFACTURER PART NUMBER") "GRM155R71C104KA88D")
      )
      (libsource (lib "LimeFPGAboard_schLib") (part "Cap_0603"))
    )
    (comp (ref "C501")
      (value "100nF, 16V")
      (footprint "CAP0402")
      (fields
        (field (name "TOLERANCE") "10 %")
        (field (name "MANUFACTURER") "Murata Electronics")
        (field (name "MANUFACTURER PART NUMBER") "GRM155R71C104KA88D")
      )
      (libsource (lib "LimeFPGAboard_schLib") (part "Cap_0603"))
    )
    (comp (ref "C502")
      (value "100nF, 16V")
      (footprint "CAP0402")
      (fields
        (field (name "TOLERANCE") "10 %")
        (field (name "MANUFACTURER") "Murata Electronics")
        (field (name "MANUFACTURER PART NUMBER") "GRM155R71C104KA88D")
      )
      (libsource (lib "LimeFPGAboard_schLib") (part "Cap_0603"))
    )
    (comp (ref "C503")
      (value "100nF, 16V")
      (footprint "CAP0402")
      (fields
        (field (name "TOLERANCE") "10 %")
        (field (name "MANUFACTURER") "Murata Electronics")
        (field (name "MANUFACTURER PART NUMBER") "GRM155R71C104KA88D")
      )
      (libsource (lib "LimeFPGAboard_schLib") (part "Cap_0603"))
    )
    (comp (ref "C504")
      (value "100nF, 16V")
      (footprint "CAP0402")
      (fields
        (field (name "TOLERANCE") "10 %")
        (field (name "MANUFACTURER") "Murata Electronics")
        (field (name "MANUFACTURER PART NUMBER") "GRM155R71C104KA88D")
      )
      (libsource (lib "LimeFPGAboard_schLib") (part "Cap_0603"))
    )
    (comp (ref "C505")
      (value "100nF, 16V")
      (footprint "CAP0402")
      (fields
        (field (name "TOLERANCE") "10 %")
        (field (name "MANUFACTURER") "Murata Electronics")
        (field (name "MANUFACTURER PART NUMBER") "GRM155R71C104KA88D")
      )
      (libsource (lib "LimeFPGAboard_schLib") (part "Cap_0603"))
    )
    (comp (ref "C506")
      (value "100nF, 16V")
      (footprint "CAP0402")
      (fields
        (field (name "TOLERANCE") "10 %")
        (field (name "MANUFACTURER") "Murata Electronics")
        (field (name "MANUFACTURER PART NUMBER") "GRM155R71C104KA88D")
      )
      (libsource (lib "LimeFPGAboard_schLib") (part "Cap_0603"))
    )
    (comp (ref "C507")
      (value "100nF, 16V")
      (footprint "CAP0402")
      (fields
        (field (name "TOLERANCE") "10 %")
        (field (name "MANUFACTURER") "Murata Electronics")
        (field (name "MANUFACTURER PART NUMBER") "GRM155R71C104KA88D")
      )
      (libsource (lib "LimeFPGAboard_schLib") (part "Cap_0603"))
    )
    (comp (ref "C508")
      (value "100nF, 16V")
      (footprint "CAP0402")
      (fields
        (field (name "TOLERANCE") "10 %")
        (field (name "MANUFACTURER") "Murata Electronics")
        (field (name "MANUFACTURER PART NUMBER") "GRM155R71C104KA88D")
      )
      (libsource (lib "LimeFPGAboard_schLib") (part "Cap_0603"))
    )
    (comp (ref "C509")
      (value "100nF, 16V")
      (footprint "CAP0402")
      (fields
        (field (name "TOLERANCE") "10 %")
        (field (name "MANUFACTURER") "Murata Electronics")
        (field (name "MANUFACTURER PART NUMBER") "GRM155R71C104KA88D")
      )
      (libsource (lib "LimeFPGAboard_schLib") (part "Cap_0603"))
    )
    (comp (ref "C510")
      (value "100nF, 16V")
      (footprint "CAP0402")
      (fields
        (field (name "TOLERANCE") "10 %")
        (field (name "MANUFACTURER") "Murata Electronics")
        (field (name "MANUFACTURER PART NUMBER") "GRM155R71C104KA88D")
      )
      (libsource (lib "LimeFPGAboard_schLib") (part "Cap_0603"))
    )
    (comp (ref "C511")
      (value "100nF, 16V")
      (footprint "CAP0402")
      (fields
        (field (name "TOLERANCE") "10 %")
        (field (name "MANUFACTURER") "Murata Electronics")
        (field (name "MANUFACTURER PART NUMBER") "GRM155R71C104KA88D")
      )
      (libsource (lib "LimeFPGAboard_schLib") (part "Cap_0603"))
    )
    (comp (ref "C512")
      (value "100nF, 16V")
      (footprint "CAP0402")
      (fields
        (field (name "TOLERANCE") "10 %")
        (field (name "MANUFACTURER") "Murata Electronics")
        (field (name "MANUFACTURER PART NUMBER") "GRM155R71C104KA88D")
      )
      (libsource (lib "LimeFPGAboard_schLib") (part "Cap_0603"))
    )
    (comp (ref "C513")
      (value "100nF, 16V")
      (footprint "CAP0402")
      (fields
        (field (name "TOLERANCE") "10 %")
        (field (name "MANUFACTURER") "Murata Electronics")
        (field (name "MANUFACTURER PART NUMBER") "GRM155R71C104KA88D")
      )
      (libsource (lib "LimeFPGAboard_schLib") (part "Cap_0603"))
    )
    (comp (ref "C514")
      (value "100nF, 16V")
      (footprint "CAP0402")
      (fields
        (field (name "TOLERANCE") "10 %")
        (field (name "MANUFACTURER") "Murata Electronics")
        (field (name "MANUFACTURER PART NUMBER") "GRM155R71C104KA88D")
      )
      (libsource (lib "LimeFPGAboard_schLib") (part "Cap_0603"))
    )
    (comp (ref "C515")
      (value "100nF, 16V")
      (footprint "CAP0402")
      (fields
        (field (name "TOLERANCE") "10 %")
        (field (name "MANUFACTURER") "Murata Electronics")
        (field (name "MANUFACTURER PART NUMBER") "GRM155R71C104KA88D")
      )
      (libsource (lib "LimeFPGAboard_schLib") (part "Cap_0603"))
    )
    (comp (ref "C516")
      (value "100nF, 16V")
      (footprint "CAP0402")
      (fields
        (field (name "TOLERANCE") "10 %")
        (field (name "MANUFACTURER") "Murata Electronics")
        (field (name "MANUFACTURER PART NUMBER") "GRM155R71C104KA88D")
      )
      (libsource (lib "LimeFPGAboard_schLib") (part "Cap_0603"))
    )
    (comp (ref "C517")
      (value "100nF, 16V")
      (footprint "CAP0402")
      (fields
        (field (name "TOLERANCE") "10 %")
        (field (name "MANUFACTURER") "Murata Electronics")
        (field (name "MANUFACTURER PART NUMBER") "GRM155R71C104KA88D")
      )
      (libsource (lib "LimeFPGAboard_schLib") (part "Cap_0603"))
    )
    (comp (ref "C518")
      (value "100nF, 16V")
      (footprint "CAP0402")
      (fields
        (field (name "TOLERANCE") "10 %")
        (field (name "MANUFACTURER") "Murata Electronics")
        (field (name "MANUFACTURER PART NUMBER") "GRM155R71C104KA88D")
      )
      (libsource (lib "LimeFPGAboard_schLib") (part "Cap_0603"))
    )
    (comp (ref "C519")
      (value "100nF, 16V")
      (footprint "CAP0402")
      (fields
        (field (name "TOLERANCE") "10 %")
        (field (name "MANUFACTURER") "Murata Electronics")
        (field (name "MANUFACTURER PART NUMBER") "GRM155R71C104KA88D")
      )
      (libsource (lib "LimeFPGAboard_schLib") (part "Cap_0603"))
    )
    (comp (ref "C520")
      (value "100nF, 16V")
      (footprint "CAP0402")
      (fields
        (field (name "TOLERANCE") "10 %")
        (field (name "MANUFACTURER") "Murata Electronics")
        (field (name "MANUFACTURER PART NUMBER") "GRM155R71C104KA88D")
      )
      (libsource (lib "LimeFPGAboard_schLib") (part "Cap_0603"))
    )
    (comp (ref "C521")
      (value "100nF, 16V")
      (footprint "CAP0402")
      (fields
        (field (name "TOLERANCE") "10 %")
        (field (name "MANUFACTURER") "Murata Electronics")
        (field (name "MANUFACTURER PART NUMBER") "GRM155R71C104KA88D")
      )
      (libsource (lib "LimeFPGAboard_schLib") (part "Cap_0603"))
    )
    (comp (ref "C522")
      (value "100nF, 16V")
      (footprint "CAP0402")
      (fields
        (field (name "TOLERANCE") "10 %")
        (field (name "MANUFACTURER") "Murata Electronics")
        (field (name "MANUFACTURER PART NUMBER") "GRM155R71C104KA88D")
      )
      (libsource (lib "LimeFPGAboard_schLib") (part "Cap_0603"))
    )
    (comp (ref "C523")
      (value "100nF, 16V")
      (footprint "CAP0402")
      (fields
        (field (name "TOLERANCE") "10 %")
        (field (name "MANUFACTURER") "Murata Electronics")
        (field (name "MANUFACTURER PART NUMBER") "GRM155R71C104KA88D")
      )
      (libsource (lib "LimeFPGAboard_schLib") (part "Cap_0603"))
    )
    (comp (ref "C524")
      (value "100nF, 16V")
      (footprint "CAP0402")
      (fields
        (field (name "TOLERANCE") "10 %")
        (field (name "MANUFACTURER") "Murata Electronics")
        (field (name "MANUFACTURER PART NUMBER") "GRM155R71C104KA88D")
      )
      (libsource (lib "LimeFPGAboard_schLib") (part "Cap_0603"))
    )
    (comp (ref "C525")
      (value "100nF, 16V")
      (footprint "CAP0402")
      (fields
        (field (name "TOLERANCE") "10 %")
        (field (name "MANUFACTURER") "Murata Electronics")
        (field (name "MANUFACTURER PART NUMBER") "GRM155R71C104KA88D")
      )
      (libsource (lib "LimeFPGAboard_schLib") (part "Cap_0603"))
    )
    (comp (ref "C526")
      (value "100nF, 16V")
      (footprint "CAP0402")
      (fields
        (field (name "TOLERANCE") "10 %")
        (field (name "MANUFACTURER") "Murata Electronics")
        (field (name "MANUFACTURER PART NUMBER") "GRM155R71C104KA88D")
      )
      (libsource (lib "LimeFPGAboard_schLib") (part "Cap_0603"))
    )
    (comp (ref "C527")
      (value "100nF, 16V")
      (footprint "CAP0402")
      (fields
        (field (name "TOLERANCE") "10 %")
        (field (name "MANUFACTURER") "Murata Electronics")
        (field (name "MANUFACTURER PART NUMBER") "GRM155R71C104KA88D")
      )
      (libsource (lib "LimeFPGAboard_schLib") (part "Cap_0603"))
    )
    (comp (ref "C528")
      (value "100nF, 16V")
      (footprint "CAP0402")
      (fields
        (field (name "TOLERANCE") "10 %")
        (field (name "MANUFACTURER") "Murata Electronics")
        (field (name "MANUFACTURER PART NUMBER") "GRM155R71C104KA88D")
      )
      (libsource (lib "LimeFPGAboard_schLib") (part "Cap_0603"))
    )
    (comp (ref "C529")
      (value "100nF, 16V")
      (footprint "CAP0402")
      (fields
        (field (name "TOLERANCE") "10 %")
        (field (name "MANUFACTURER") "Murata Electronics")
        (field (name "MANUFACTURER PART NUMBER") "GRM155R71C104KA88D")
      )
      (libsource (lib "LimeFPGAboard_schLib") (part "Cap_0603"))
    )
    (comp (ref "C530")
      (value "100nF, 16V")
      (footprint "CAP0402")
      (fields
        (field (name "TOLERANCE") "10 %")
        (field (name "MANUFACTURER") "Murata Electronics")
        (field (name "MANUFACTURER PART NUMBER") "GRM155R71C104KA88D")
      )
      (libsource (lib "LimeFPGAboard_schLib") (part "Cap_0603"))
    )
    (comp (ref "C531")
      (value "100nF, 16V")
      (footprint "CAP0402")
      (fields
        (field (name "TOLERANCE") "10 %")
        (field (name "MANUFACTURER") "Murata Electronics")
        (field (name "MANUFACTURER PART NUMBER") "GRM155R71C104KA88D")
      )
      (libsource (lib "LimeFPGAboard_schLib") (part "Cap_0603"))
    )
    (comp (ref "C532")
      (value "100nF, 16V")
      (footprint "CAP0402")
      (fields
        (field (name "TOLERANCE") "10 %")
        (field (name "MANUFACTURER") "Murata Electronics")
        (field (name "MANUFACTURER PART NUMBER") "GRM155R71C104KA88D")
      )
      (libsource (lib "LimeFPGAboard_schLib") (part "Cap_0603"))
    )
    (comp (ref "C533")
      (value "100nF, 16V")
      (footprint "CAP0402")
      (fields
        (field (name "TOLERANCE") "10 %")
        (field (name "MANUFACTURER") "Murata Electronics")
        (field (name "MANUFACTURER PART NUMBER") "GRM155R71C104KA88D")
      )
      (libsource (lib "LimeFPGAboard_schLib") (part "Cap_0603"))
    )
    (comp (ref "C534")
      (value "100nF, 16V")
      (footprint "CAP0402")
      (fields
        (field (name "TOLERANCE") "10 %")
        (field (name "MANUFACTURER") "Murata Electronics")
        (field (name "MANUFACTURER PART NUMBER") "GRM155R71C104KA88D")
      )
      (libsource (lib "LimeFPGAboard_schLib") (part "Cap_0603"))
    )
    (comp (ref "C535")
      (value "100nF, 16V")
      (footprint "CAP0402")
      (fields
        (field (name "TOLERANCE") "10 %")
        (field (name "MANUFACTURER") "Murata Electronics")
        (field (name "MANUFACTURER PART NUMBER") "GRM155R71C104KA88D")
      )
      (libsource (lib "LimeFPGAboard_schLib") (part "Cap_0603"))
    )
  )
  (nets
    (net (code "1") (name "GND") (class "Default")
      (node (ref "C390") (pin "2") (pinfunction "2_2") (pintype "passive"))
      (node (ref "C391") (pin "2") (pinfunction "2_2") (pintype "passive"))
      (node (ref "C392") (pin "2") (pinfunction "2_2") (pintype "passive"))
      (node (ref "C393") (pin "2") (pinfunction "2_2") (pintype "passive"))
      (node (ref "C394") (pin "2") (pinfunction "2_2") (pintype "passive"))
      (node (ref "C395") (pin "2") (pinfunction "2_2") (pintype "passive"))
      (node (ref "C396") (pin "2") (pinfunction "2_2") (pintype "passive"))
      (node (ref "C397") (pin "2") (pinfunction "2_2") (pintype "passive"))
      (node (ref "C398") (pin "2") (pinfunction "2_2") (pintype "passive"))
      (node (ref "C399") (pin "2") (pinfunction "2_2") (pintype "passive"))
      (node (ref "C400") (pin "2") (pinfunction "2_2") (pintype "passive"))
      (node (ref "C401") (pin "2") (pinfunction "2_2") (pintype "passive"))
      (node (ref "C402") (pin "2") (pinfunction "2_2") (pintype "passive"))
      (node (ref "C403") (pin "2") (pinfunction "2_2") (pintype "passive"))
      (node (ref "C404") (pin "2") (pinfunction "2_2") (pintype "passive"))
      (node (ref "C405") (pin "2") (pinfunction "2_2") (pintype "passive"))
      (node (ref "C406") (pin "2") (pinfunction "2_2") (pintype "passive"))
      (node (ref "C407") (pin "2") (pinfunction "2_2") (pintype "passive"))
      (node (ref "C408") (pin "2") (pinfunction "2_2") (pintype "passive"))
      (node (ref "C409") (pin "2") (pinfunction "2_2") (pintype "passive"))
      (node (ref "C410") (pin "2") (pinfunction "2_2") (pintype "passive"))
      (node (ref "C411") (pin "2") (pinfunction "2_2") (pintype "passive"))
      (node (ref "C412") (pin "2") (pinfunction "2_2") (pintype "passive"))
      (node (ref "C413") (pin "2") (pinfunction "2_2") (pintype "passive"))
      (node (ref "C414") (pin "2") (pinfunction "2_2") (pintype "passive"))
      (node (ref "C415") (pin "2") (pinfunction "2_2") (pintype "passive"))
      (node (ref "C416") (pin "2") (pinfunction "2_2") (pintype "passive"))
      (node (ref "C417") (pin "2") (pinfunction "2_2") (pintype "passive"))
      (node (ref "C418") (pin "2") (pinfunction "2_2") (pintype "passive"))
      (node (ref "C419") (pin "2") (pinfunction "2_2") (pintype "passive"))
      (node (ref "C420") (pin "2") (pinfunction "2_2") (pintype "passive"))
      (node (ref "C421") (pin "2") (pinfunction "2_2") (pintype "passive"))
      (node (ref "C422") (pin "2") (pinfunction "2_2") (pintype "passive"))
      (node (ref "C423") (pin "2") (pinfunction "2_2") (pintype "passive"))
      (node (ref "C424") (pin "2") (pinfunction "2_2") (pintype "passive"))
      (node (ref "C425") (pin "2") (pinfunction "2_2") (pintype "passive"))
      (node (ref "C426") (pin "2") (pinfunction "2_2") (pintype "passive"))
      (node (ref "C427") (pin "2") (pinfunction "2_2") (pintype "passive"))
      (node (ref "C428") (pin "2") (pinfunction "2_2") (pintype "passive"))
      (node (ref "C429") (pin "2") (pinfunction "2_2") (pintype "passive"))
      (node (ref "C430") (pin "2") (pinfunction "2_2") (pintype "passive"))
      (node (ref "C431") (pin "2") (pinfunction "2_2") (pintype "passive"))
      (node (ref "C432") (pin "2") (pinfunction "2_2") (pintype "passive"))
      (node (ref "C433") (pin "2") (pinfunction "2_2") (pintype "passive"))
      (node (ref "C434") (pin "2") (pinfunction "2_2") (pintype "passive"))
      (node (ref "C435") (pin "2") (pinfunction "2_2") (pintype "passive"))
      (node (ref "C436") (pin "2") (pinfunction "2_2") (pintype "passive"))
      (node (ref "C437") (pin "2") (pinfunction "2_2") (pintype "passive"))
      (node (ref "C438") (pin "2") (pinfunction "2_2") (pintype "passive"))
      (node (ref "C439") (pin "2") (pinfunction "2_2") (pintype "passive"))
      (node (ref "C440") (pin "2") (pinfunction "2_2") (pintype "passive"))
      (node (ref "C441") (pin "2") (pinfunction "2_2") (pintype "passive"))
      (node (ref "C442") (pin "2") (pinfunction "2_2") (pintype "passive"))
      (node (ref "C443") (pin "2") (pinfunction "2_2") (pintype "passive"))
      (node (ref "C444") (pin "2") (pinfunction "2_2") (pintype "passive"))
      (node (ref "C445") (pin "2") (pinfunction "2_2") (pintype "passive"))
      (node (ref "C446") (pin "2") (pinfunction "2_2") (pintype "passive"))
      (node (ref "C447") (pin "2") (pinfunction "2_2") (pintype "passive"))
      (node (ref "C448") (pin "2") (pinfunction "2_2") (pintype "passive"))
      (node (ref "C449") (pin "2") (pinfunction "2_2") (pintype "passive"))
      (node (ref "C450") (pin "2") (pinfunction "2_2") (pintype "passive"))
      (node (ref "C451") (pin "2") (pinfunction "2_2") (pintype "passive"))
      (node (ref "C452") (pin "2") (pinfunction "2_2") (pintype "passive"))
      (node (ref "C453") (pin "2") (pinfunction "2_2") (pintype "passive"))
      (node (ref "C454") (pin "2") (pinfunction "2_2") (pintype "passive"))
      (node (ref "C455") (pin "2") (pinfunction "2_2") (pintype "passive"))
      (node (ref "C456") (pin "2") (pinfunction "2_2") (pintype "passive"))
      (node (ref "C457") (pin "2") (pinfunction "2_2") (pintype "passive"))
      (node (ref "C458") (pin "2") (pinfunction "2_2") (pintype "passive"))
      (node (ref "C459") (pin "2") (pinfunction "2_2") (pintype "passive"))
      (node (ref "C460") (pin "2") (pinfunction "2_2") (pintype "passive"))
      (node (ref "C461") (pin "2") (pinfunction "2_2") (pintype "passive"))
      (node (ref "C462") (pin "2") (pinfunction "2_2") (pintype "passive"))
      (node (ref "C463") (pin "2") (pinfunction "2_2") (pintype "passive"))
      (node (ref "C464") (pin "2") (pinfunction "2_2") (pintype "passive"))
      (node (ref "C465") (pin "2") (pinfunction "2_2") (pintype "passive"))
      (node (ref "C466") (pin "2") (pinfunction "2_2") (pintype "passive"))
      (node (ref "C467") (pin "2") (pinfunction "2_2") (pintype "passive"))
      (node (ref "C468") (pin "2") (pinfunction "2_2") (pintype "passive"))
      (node (ref "C469") (pin "2") (pinfunction "2_2") (pintype "passive"))
      (node (ref "C470") (pin "2") (pinfunction "2_2") (pintype "passive"))
      (node (ref "C471") (pin "2") (pinfunction "2_2") (pintype "passive"))
      (node (ref "C472") (pin "2") (pinfunction "2_2") (pintype "passive"))
      (node (ref "C473") (pin "2") (pinfunction "2_2") (pintype "passive"))
      (node (ref "C474") (pin "2") (pinfunction "2_2") (pintype "passive"))
      (node (ref "C475") (pin "2") (pinfunction "2_2") (pintype "passive"))
      (node (ref "C476") (pin "2") (pinfunction "2_2") (pintype "passive"))
      (node (ref "C477") (pin "2") (pinfunction "2_2") (pintype "passive"))
      (node (ref "C478") (pin "2") (pinfunction "2_2") (pintype "passive"))
      (node (ref "C479") (pin "2") (pinfunction "2_2") (pintype "passive"))
      (node (ref "C480") (pin "2") (pinfunction "2_2") (pintype "passive"))
      (node (ref "C481") (pin "2") (pinfunction "2_2") (pintype "passive"))
      (node (ref "C482") (pin "2") (pinfunction "2_2") (pintype "passive"))
      (node (ref "C483") (pin "2") (pinfunction "2_2") (pintype "passive"))
      (node (ref "C484") (pin "2") (pinfunction "2_2") (pintype "passive"))
      (node (ref "C485") (pin "2") (pinfunction "2_2") (pintype "passive"))
      (node (ref "C486") (pin "2") (pinfunction "2_2") (pintype "passive"))
      (node (ref "C487") (pin "2") (pinfunction "2_2") (pintype "passive"))
      (node (ref "C488") (pin "2") (pinfunction "2_2") (pintype "passive"))
      (node (ref "C489") (pin "2") (pinfunction "2_2") (pintype "passive"))
      (node (ref "C490") (pin "2") (pinfunction "2_2") (pintype "passive"))
      (node (ref "C491") (pin "2") (pinfunction "2_2") (pintype "passive"))
      (node (ref "C492") (pin "2") (pinfunction "2_2") (pintype "passive"))
      (node (ref "C493") (pin "2") (pinfunction "2_2") (pintype "passive"))
      (node (ref "C494") (pin "2") (pinfunction "2_2") (pintype "passive"))
      (node (ref "C495") (pin "2") (pinfunction "2_2") (pintype "passive"))
      (node (ref "C496") (pin "2") (pinfunction "2_2") (pintype "passive"))
      (node (ref "C497") (pin "2") (pinfunction "2_2") (pintype "passive"))
      (node (ref "C498") (pin "2") (pinfunction "2_2") (pintype "passive"))
      (node (ref "C499") (pin "2") (pinfunction "2_2") (pintype "passive"))
      (node (ref "C500") (pin "2") (pinfunction "2_2") (pintype "passive"))
      (node (ref "C501") (pin "2") (pinfunction "2_2") (pintype "passive"))
      (node (ref "C502") (pin "2") (pinfunction "2_2") (pintype "passive"))
      (node (ref "C503") (pin "2") (pinfunction "2_2") (pintype "passive"))
      (node (ref "C504") (pin "2") (pinfunction "2_2") (pintype "passive"))
      (node (ref "C505") (pin "2") (pinfunction "2_2") (pintype "passive"))
      (node (ref "C506") (pin "2") (pinfunction "2_2") (pintype "passive"))
      (node (ref "C507") (pin "2") (pinfunction "2_2") (pintype "passive"))
      (node (ref "C508") (pin "2") (pinfunction "2_2") (pintype "passive"))
      (node (ref "C509") (pin "2") (pinfunction "2_2") (pintype "passive"))
      (node (ref "C510") (pin "2") (pinfunction "2_2") (pintype "passive"))
      (node (ref "C511") (pin "2") (pinfunction "2_2") (pintype "passive"))
      (node (ref "C512") (pin "2") (pinfunction "2_2") (pintype "passive"))
      (node (ref "C513") (pin "2") (pinfunction "2_2") (pintype "passive"))
      (node (ref "C514") (pin "2") (pinfunction "2_2") (pintype "passive"))
      (node (ref "C515") (pin "2") (pinfunction "2_2") (pintype "passive"))
      (node (ref "C516") (pin "2") (pinfunction "2_2") (pintype "passive"))
      (node (ref "C517") (pin "2") (pinfunction "2_2") (pintype "passive"))
      (node (ref "C518") (pin "2") (pinfunction "2_2") (pintype "passive"))
      (node (ref "C519") (pin "2") (pinfunction "2_2") (pintype "passive"))
      (node (ref "C520") (pin "2") (pinfunction "2_2") (pintype "passive"))
      (node (ref "C521") (pin "2") (pinfunction "2_2") (pintype "passive"))
      (node (ref "C522") (pin "2") (pinfunction "2_2") (pintype "passive"))
      (node (ref "C523") (pin "2") (pinfunction "2_2") (pintype "passive"))
      (node (ref "C524") (pin "2") (pinfunction "2_2") (pintype "passive"))
      (node (ref "C525") (pin "2") (pinfunction "2_2") (pintype "passive"))
      (node (ref "C526") (pin "2") (pinfunction "2_2") (pintype "passive"))
      (node (ref "C527") (pin "2") (pinfunction "2_2") (pintype "passive"))
      (node (ref "C528") (pin "2") (pinfunction "2_2") (pintype "passive"))
      (node (ref "C529") (pin "2") (pinfunction "2_2") (pintype "passive"))
      (node (ref "C530") (pin "2") (pinfunction "2_2") (pintype "passive"))
      (node (ref "C531") (pin "2") (pinfunction "2_2") (pintype "passive"))
      (node (ref "C532") (pin "2") (pinfunction "2_2") (pintype "passive"))
      (node (ref "C533") (pin "2") (pinfunction "2_2") (pintype "passive"))
      (node (ref "C534") (pin "2") (pinfunction "2_2") (pintype "passive"))
      (node (ref "C535") (pin "2") (pinfunction "2_2") (pintype "passive"))
    )
    (net (code "2") (name "VCC1P1") (class "Default")
      (node (ref "C413") (pin "1") (pinfunction "1_1") (pintype "passive"))
      (node (ref "C414") (pin "1") (pinfunction "1_1") (pintype "passive"))
      (node (ref "C415") (pin "1") (pinfunction "1_1") (pintype "passive"))
      (node (ref "C416") (pin "1") (pinfunction "1_1") (pintype "passive"))
      (node (ref "C417") (pin "1") (pinfunction "1_1") (pintype "passive"))
      (node (ref "C418") (pin "1") (pinfunction "1_1") (pintype "passive"))
      (node (ref "C419") (pin "1") (pinfunction "1_1") (pintype "passive"))
      (node (ref "C420") (pin "1") (pinfunction "1_1") (pintype "passive"))
      (node (ref "C421") (pin "1") (pinfunction "1_1") (pintype "passive"))
      (node (ref "C422") (pin "1") (pinfunction "1_1") (pintype "passive"))
      (node (ref "C423") (pin "1") (pinfunction "1_1") (pintype "passive"))
      (node (ref "C424") (pin "1") (pinfunction "1_1") (pintype "passive"))
      (node (ref "C425") (pin "1") (pinfunction "1_1") (pintype "passive"))
      (node (ref "C426") (pin "1") (pinfunction "1_1") (pintype "passive"))
      (node (ref "C427") (pin "1") (pinfunction "1_1") (pintype "passive"))
      (node (ref "C428") (pin "1") (pinfunction "1_1") (pintype "passive"))
      (node (ref "C429") (pin "1") (pinfunction "1_1") (pintype "passive"))
      (node (ref "C430") (pin "1") (pinfunction "1_1") (pintype "passive"))
      (node (ref "C431") (pin "1") (pinfunction "1_1") (pintype "passive"))
      (node (ref "C432") (pin "1") (pinfunction "1_1") (pintype "passive"))
      (node (ref "C433") (pin "1") (pinfunction "1_1") (pintype "passive"))
      (node (ref "C434") (pin "1") (pinfunction "1_1") (pintype "passive"))
      (node (ref "C435") (pin "1") (pinfunction "1_1") (pintype "passive"))
      (node (ref "C436") (pin "1") (pinfunction "1_1") (pintype "passive"))
      (node (ref "C437") (pin "1") (pinfunction "1_1") (pintype "passive"))
      (node (ref "C438") (pin "1") (pinfunction "1_1") (pintype "passive"))
      (node (ref "C439") (pin "1") (pinfunction "1_1") (pintype "passive"))
      (node (ref "C440") (pin "1") (pinfunction "1_1") (pintype "passive"))
      (node (ref "C441") (pin "1") (pinfunction "1_1") (pintype "passive"))
      (node (ref "C442") (pin "1") (pinfunction "1_1") (pintype "passive"))
    )
    (net (code "3") (name "VCC1P1E_FPGA") (class "Default")
      (node (ref "C403") (pin "1") (pinfunction "1_1") (pintype "passive"))
      (node (ref "C404") (pin "1") (pinfunction "1_1") (pintype "passive"))
      (node (ref "C405") (pin "1") (pinfunction "1_1") (pintype "passive"))
      (node (ref "C406") (pin "1") (pinfunction "1_1") (pintype "passive"))
      (node (ref "C407") (pin "1") (pinfunction "1_1") (pintype "passive"))
      (node (ref "C408") (pin "1") (pinfunction "1_1") (pintype "passive"))
      (node (ref "C409") (pin "1") (pinfunction "1_1") (pintype "passive"))
      (node (ref "C410") (pin "1") (pinfunction "1_1") (pintype "passive"))
    )
    (net (code "4") (name "VCC1P1L_FPGA") (class "Default")
      (node (ref "C395") (pin "1") (pinfunction "1_1") (pintype "passive"))
      (node (ref "C396") (pin "1") (pinfunction "1_1") (pintype "passive"))
      (node (ref "C397") (pin "1") (pinfunction "1_1") (pintype "passive"))
      (node (ref "C398") (pin "1") (pinfunction "1_1") (pintype "passive"))
    )
    (net (code "5") (name "VCC1P5") (class "Default")
      (node (ref "C443") (pin "1") (pinfunction "1_1") (pintype "passive"))
      (node (ref "C444") (pin "1") (pinfunction "1_1") (pintype "passive"))
      (node (ref "C445") (pin "1") (pinfunction "1_1") (pintype "passive"))
      (node (ref "C446") (pin "1") (pinfunction "1_1") (pintype "passive"))
      (node (ref "C447") (pin "1") (pinfunction "1_1") (pintype "passive"))
      (node (ref "C448") (pin "1") (pinfunction "1_1") (pintype "passive"))
      (node (ref "C449") (pin "1") (pinfunction "1_1") (pintype "passive"))
      (node (ref "C450") (pin "1") (pinfunction "1_1") (pintype "passive"))
      (node (ref "C451") (pin "1") (pinfunction "1_1") (pintype "passive"))
      (node (ref "C452") (pin "1") (pinfunction "1_1") (pintype "passive"))
      (node (ref "C453") (pin "1") (pinfunction "1_1") (pintype "passive"))
      (node (ref "C454") (pin "1") (pinfunction "1_1") (pintype "passive"))
      (node (ref "C455") (pin "1") (pinfunction "1_1") (pintype "passive"))
      (node (ref "C456") (pin "1") (pinfunction "1_1") (pintype "passive"))
      (node (ref "C457") (pin "1") (pinfunction "1_1") (pintype "passive"))
      (node (ref "C458") (pin "1") (pinfunction "1_1") (pintype "passive"))
      (node (ref "C459") (pin "1") (pinfunction "1_1") (pintype "passive"))
      (node (ref "C460") (pin "1") (pinfunction "1_1") (pintype "passive"))
      (node (ref "C461") (pin "1") (pinfunction "1_1") (pintype "passive"))
      (node (ref "C462") (pin "1") (pinfunction "1_1") (pintype "passive"))
      (node (ref "C463") (pin "1") (pinfunction "1_1") (pintype "passive"))
      (node (ref "C464") (pin "1") (pinfunction "1_1") (pintype "passive"))
      (node (ref "C465") (pin "1") (pinfunction "1_1") (pintype "passive"))
      (node (ref "C466") (pin "1") (pinfunction "1_1") (pintype "passive"))
      (node (ref "C467") (pin "1") (pinfunction "1_1") (pintype "passive"))
      (node (ref "C468") (pin "1") (pinfunction "1_1") (pintype "passive"))
      (node (ref "C469") (pin "1") (pinfunction "1_1") (pintype "passive"))
      (node (ref "C470") (pin "1") (pinfunction "1_1") (pintype "passive"))
      (node (ref "C471") (pin "1") (pinfunction "1_1") (pintype "passive"))
      (node (ref "C472") (pin "1") (pinfunction "1_1") (pintype "passive"))
      (node (ref "C473") (pin "1") (pinfunction "1_1") (pintype "passive"))
      (node (ref "C474") (pin "1") (pinfunction "1_1") (pintype "passive"))
      (node (ref "C475") (pin "1") (pinfunction "1_1") (pintype "passive"))
      (node (ref "C476") (pin "1") (pinfunction "1_1") (pintype "passive"))
      (node (ref "C477") (pin "1") (pinfunction "1_1") (pintype "passive"))
      (node (ref "C478") (pin "1") (pinfunction "1_1") (pintype "passive"))
    )
    (net (code "6") (name "VCC1P8") (class "Default")
      (node (ref "C399") (pin "1") (pinfunction "1_1") (pintype "passive"))
      (node (ref "C400") (pin "1") (pinfunction "1_1") (pintype "passive"))
      (node (ref "C401") (pin "1") (pinfunction "1_1") (pintype "passive"))
      (node (ref "C402") (pin "1") (pinfunction "1_1") (pintype "passive"))
    )
    (net (code "7") (name "VCC2P5") (class "Default")
      (node (ref "C521") (pin "1") (pinfunction "1_1") (pintype "passive"))
      (node (ref "C522") (pin "1") (pinfunction "1_1") (pintype "passive"))
      (node (ref "C523") (pin "1") (pinfunction "1_1") (pintype "passive"))
      (node (ref "C524") (pin "1") (pinfunction "1_1") (pintype "passive"))
      (node (ref "C525") (pin "1") (pinfunction "1_1") (pintype "passive"))
      (node (ref "C526") (pin "1") (pinfunction "1_1") (pintype "passive"))
      (node (ref "C527") (pin "1") (pinfunction "1_1") (pintype "passive"))
      (node (ref "C528") (pin "1") (pinfunction "1_1") (pintype "passive"))
      (node (ref "C529") (pin "1") (pinfunction "1_1") (pintype "passive"))
      (node (ref "C530") (pin "1") (pinfunction "1_1") (pintype "passive"))
      (node (ref "C531") (pin "1") (pinfunction "1_1") (pintype "passive"))
      (node (ref "C532") (pin "1") (pinfunction "1_1") (pintype "passive"))
      (node (ref "C533") (pin "1") (pinfunction "1_1") (pintype "passive"))
      (node (ref "C534") (pin "1") (pinfunction "1_1") (pintype "passive"))
      (node (ref "C535") (pin "1") (pinfunction "1_1") (pintype "passive"))
    )
    (net (code "8") (name "VCC2P5H_FPGA") (class "Default")
      (node (ref "C506") (pin "1") (pinfunction "1_1") (pintype "passive"))
      (node (ref "C507") (pin "1") (pinfunction "1_1") (pintype "passive"))
      (node (ref "C508") (pin "1") (pinfunction "1_1") (pintype "passive"))
      (node (ref "C509") (pin "1") (pinfunction "1_1") (pintype "passive"))
      (node (ref "C510") (pin "1") (pinfunction "1_1") (pintype "passive"))
      (node (ref "C511") (pin "1") (pinfunction "1_1") (pintype "passive"))
      (node (ref "C512") (pin "1") (pinfunction "1_1") (pintype "passive"))
      (node (ref "C513") (pin "1") (pinfunction "1_1") (pintype "passive"))
      (node (ref "C514") (pin "1") (pinfunction "1_1") (pintype "passive"))
      (node (ref "C515") (pin "1") (pinfunction "1_1") (pintype "passive"))
      (node (ref "C516") (pin "1") (pinfunction "1_1") (pintype "passive"))
      (node (ref "C517") (pin "1") (pinfunction "1_1") (pintype "passive"))
      (node (ref "C518") (pin "1") (pinfunction "1_1") (pintype "passive"))
      (node (ref "C519") (pin "1") (pinfunction "1_1") (pintype "passive"))
      (node (ref "C520") (pin "1") (pinfunction "1_1") (pintype "passive"))
    )
    (net (code "9") (name "VCC3P3") (class "Default")
      (node (ref "C392") (pin "1") (pinfunction "1_1") (pintype "passive"))
      (node (ref "C393") (pin "1") (pinfunction "1_1") (pintype "passive"))
      (node (ref "C394") (pin "1") (pinfunction "1_1") (pintype "passive"))
    )
    (net (code "10") (name "VDIO_DAC_FPGA") (class "Default")
      (node (ref "C479") (pin "1") (pinfunction "1_1") (pintype "passive"))
      (node (ref "C480") (pin "1") (pinfunction "1_1") (pintype "passive"))
      (node (ref "C481") (pin "1") (pinfunction "1_1") (pintype "passive"))
      (node (ref "C482") (pin "1") (pinfunction "1_1") (pintype "passive"))
      (node (ref "C483") (pin "1") (pinfunction "1_1") (pintype "passive"))
      (node (ref "C484") (pin "1") (pinfunction "1_1") (pintype "passive"))
      (node (ref "C485") (pin "1") (pinfunction "1_1") (pintype "passive"))
      (node (ref "C486") (pin "1") (pinfunction "1_1") (pintype "passive"))
      (node (ref "C487") (pin "1") (pinfunction "1_1") (pintype "passive"))
      (node (ref "C488") (pin "1") (pinfunction "1_1") (pintype "passive"))
      (node (ref "C489") (pin "1") (pinfunction "1_1") (pintype "passive"))
      (node (ref "C490") (pin "1") (pinfunction "1_1") (pintype "passive"))
      (node (ref "C491") (pin "1") (pinfunction "1_1") (pintype "passive"))
    )
    (net (code "11") (name "VDIO_LMS_FPGA") (class "Default")
      (node (ref "C492") (pin "1") (pinfunction "1_1") (pintype "passive"))
      (node (ref "C493") (pin "1") (pinfunction "1_1") (pintype "passive"))
      (node (ref "C494") (pin "1") (pinfunction "1_1") (pintype "passive"))
      (node (ref "C495") (pin "1") (pinfunction "1_1") (pintype "passive"))
      (node (ref "C496") (pin "1") (pinfunction "1_1") (pintype "passive"))
      (node (ref "C497") (pin "1") (pinfunction "1_1") (pintype "passive"))
      (node (ref "C498") (pin "1") (pinfunction "1_1") (pintype "passive"))
      (node (ref "C499") (pin "1") (pinfunction "1_1") (pintype "passive"))
      (node (ref "C500") (pin "1") (pinfunction "1_1") (pintype "passive"))
      (node (ref "C501") (pin "1") (pinfunction "1_1") (pintype "passive"))
      (node (ref "C502") (pin "1") (pinfunction "1_1") (pintype "passive"))
      (node (ref "C503") (pin "1") (pinfunction "1_1") (pintype "passive"))
      (node (ref "C504") (pin "1") (pinfunction "1_1") (pintype "passive"))
      (node (ref "C505") (pin "1") (pinfunction "1_1") (pintype "passive"))
    )
    (net (code "12") (name "VREF_DDR3_BOT") (class "Default")
      (node (ref "C411") (pin "1") (pinfunction "1_1") (pintype "passive"))
      (node (ref "C412") (pin "1") (pinfunction "1_1") (pintype "passive"))
    )
    (net (code "13") (name "VREF_DDR3_TOP") (class "Default")
      (node (ref "C390") (pin "1") (pinfunction "1_1") (pintype "passive"))
      (node (ref "C391") (pin "1") (pinfunction "1_1") (pintype "passive"))
    )
  )
)
